# RC_Car_Project_Remote.net
KiCad netlist of a schematic drawn in EasyEDA
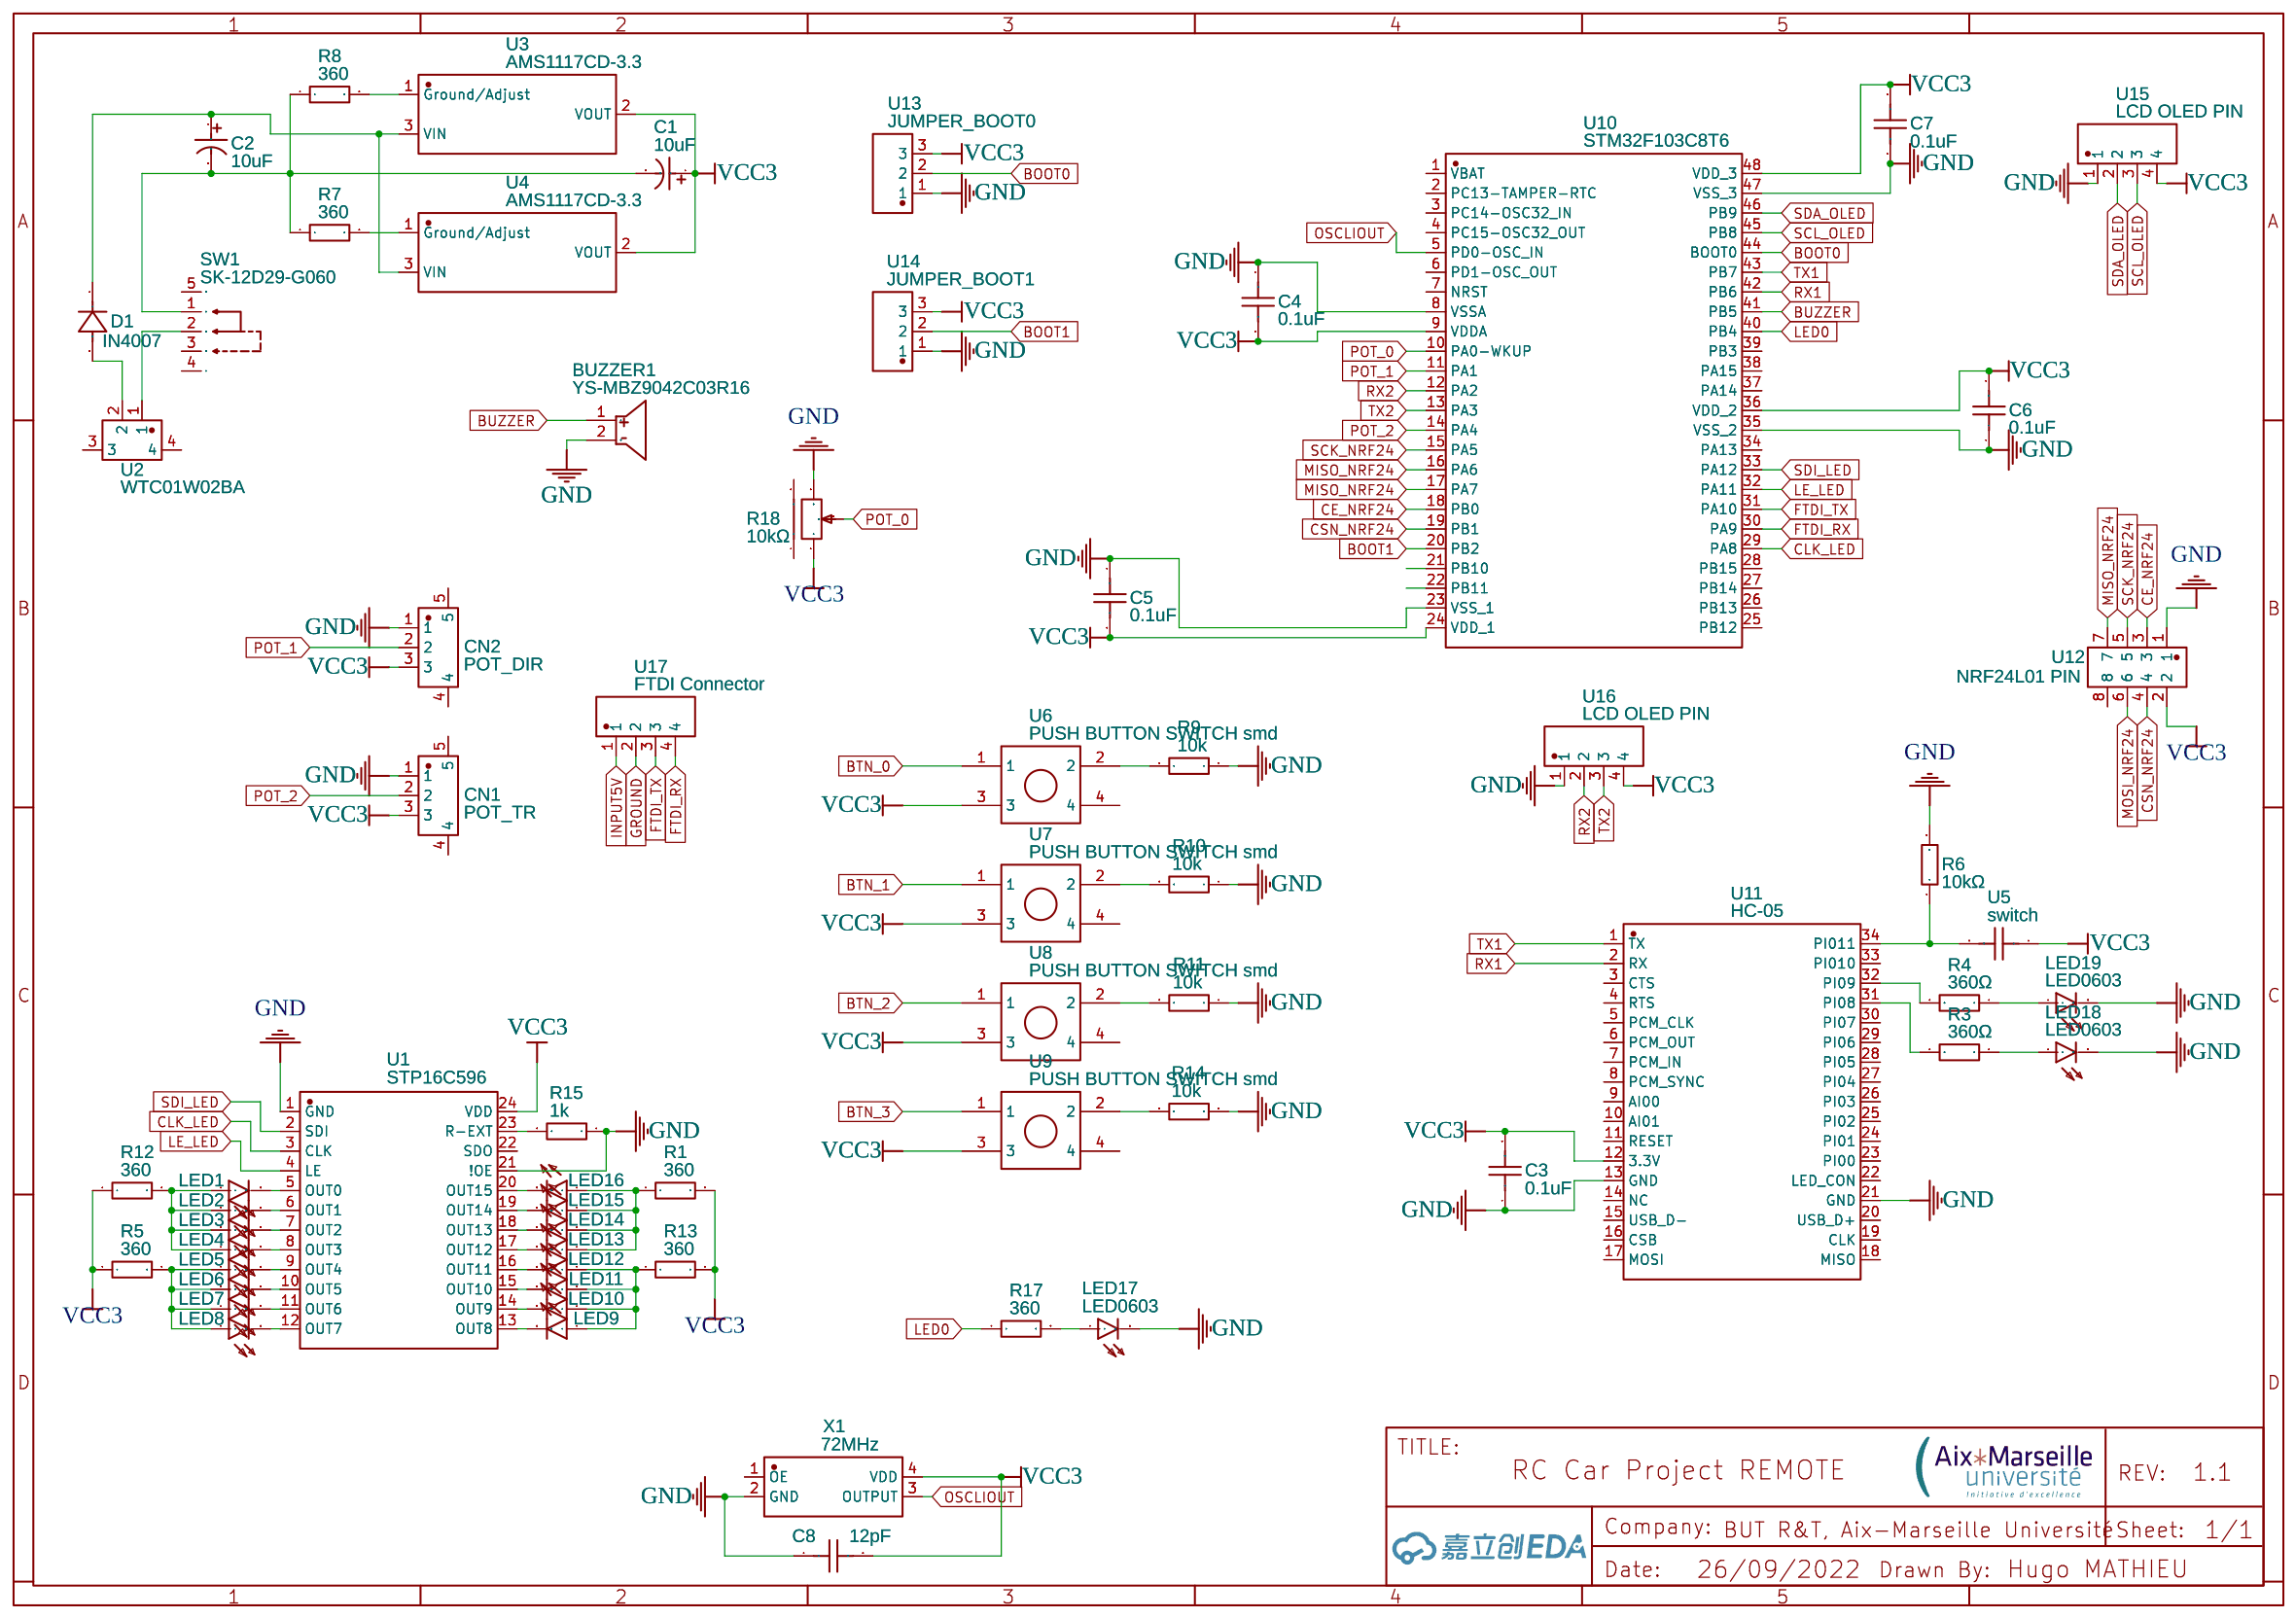
[diagram p0: schematic sheet]

(export (version "E")
  (design (tool "Eeschema 10.0.6"))
  (components
    (comp (ref "BUZZER1")
      (value "YS-MBZ9042C03R16")
      (fields (field (name "BOM_Supplier Part") "C409836"))
      (libsource (lib "") (part "YS-MBZ9042C03R16"))
    )
    (comp (ref "C1")
      (value "10uF")
      (fields
        (field (name "BOM_Manufacturer Part") "RVT1H100M0505")
        (field (name "BOM_Supplier Part") "C72487")
      )
      (libsource (lib "") (part "RVT1H100M0505_1"))
    )
    (comp (ref "C2")
      (value "10uF")
      (fields
        (field (name "BOM_Manufacturer Part") "RVT1H100M0505")
        (field (name "BOM_Supplier Part") "C72487")
      )
      (libsource (lib "") (part "RVT1H100M0505"))
    )
    (comp (ref "C3")
      (value "0.1uF")
      (fields
        (field (name "BOM_Manufacturer Part") "AC0805JRNPO9BN220")
        (field (name "BOM_Supplier Part") "C149614")
      )
      (libsource (lib "") (part "AC0805JRNPO9BN220_2"))
    )
    (comp (ref "C4")
      (value "0.1uF")
      (fields
        (field (name "BOM_Manufacturer Part") "AC0805JRNPO9BN220")
        (field (name "BOM_Supplier Part") "C149614")
      )
      (libsource (lib "") (part "AC0805JRNPO9BN220_1"))
    )
    (comp (ref "C5")
      (value "0.1uF")
      (fields
        (field (name "BOM_Manufacturer Part") "AC0805JRNPO9BN220")
        (field (name "BOM_Supplier Part") "C149614")
      )
      (libsource (lib "") (part "AC0805JRNPO9BN220_1"))
    )
    (comp (ref "C6")
      (value "0.1uF")
      (fields
        (field (name "BOM_Manufacturer Part") "AC0805JRNPO9BN220")
        (field (name "BOM_Supplier Part") "C149614")
      )
      (libsource (lib "") (part "AC0805JRNPO9BN220_2"))
    )
    (comp (ref "C7")
      (value "0.1uF")
      (fields
        (field (name "BOM_Manufacturer Part") "AC0805JRNPO9BN220")
        (field (name "BOM_Supplier Part") "C149614")
      )
      (libsource (lib "") (part "AC0805JRNPO9BN220_2"))
    )
    (comp (ref "C8")
      (value "12pF")
      (fields
        (field (name "BOM_Manufacturer Part") "AC0805JRNPO9BN220")
        (field (name "BOM_Supplier Part") "C149614")
      )
      (libsource (lib "") (part "AC0805JRNPO9BN220"))
    )
    (comp (ref "CN1")
      (value "POT_TR")
      (fields (field (name "BOM_Manufacturer Part") "1.25T-3PWT") (field (name "BOM_Supplier Part") "C22075"))
      (libsource (lib "") (part "1.25T-3PWT"))
    )
    (comp (ref "CN2")
      (value "POT_DIR")
      (fields (field (name "BOM_Manufacturer Part") "1.25T-3PWT") (field (name "BOM_Supplier Part") "C22075"))
      (libsource (lib "") (part "1.25T-3PWT"))
    )
    (comp (ref "D1")
      (value "IN4007")
      (fields (field (name "BOM_Supplier Part") "C9900004719"))
      (libsource (lib "") (part "IN4007"))
    )
    (comp (ref "LED1") (value "LED0603") (libsource (lib "") (part "LED_LEDCHIP-LED0603_1")))
    (comp (ref "LED2") (value "LED0603") (libsource (lib "") (part "LED_LEDCHIP-LED0603_1")))
    (comp (ref "LED3") (value "LED0603") (libsource (lib "") (part "LED_LEDCHIP-LED0603_1")))
    (comp (ref "LED4") (value "LED0603") (libsource (lib "") (part "LED_LEDCHIP-LED0603_1")))
    (comp (ref "LED5") (value "LED0603") (libsource (lib "") (part "LED_LEDCHIP-LED0603_1")))
    (comp (ref "LED6") (value "LED0603") (libsource (lib "") (part "LED_LEDCHIP-LED0603_1")))
    (comp (ref "LED7") (value "LED0603") (libsource (lib "") (part "LED_LEDCHIP-LED0603_1")))
    (comp (ref "LED8") (value "LED0603") (libsource (lib "") (part "LED_LEDCHIP-LED0603_1")))
    (comp (ref "LED9") (value "LED0603") (libsource (lib "") (part "LED_LEDCHIP-LED0603")))
    (comp (ref "LED10") (value "LED0603") (libsource (lib "") (part "LED_LEDCHIP-LED0603")))
    (comp (ref "LED11") (value "LED0603") (libsource (lib "") (part "LED_LEDCHIP-LED0603")))
    (comp (ref "LED12") (value "LED0603") (libsource (lib "") (part "LED_LEDCHIP-LED0603")))
    (comp (ref "LED13") (value "LED0603") (libsource (lib "") (part "LED_LEDCHIP-LED0603")))
    (comp (ref "LED14") (value "LED0603") (libsource (lib "") (part "LED_LEDCHIP-LED0603")))
    (comp (ref "LED15") (value "LED0603") (libsource (lib "") (part "LED_LEDCHIP-LED0603")))
    (comp (ref "LED16") (value "LED0603") (libsource (lib "") (part "LED_LEDCHIP-LED0603")))
    (comp (ref "LED17") (value "LED0603") (libsource (lib "") (part "LED_LEDCHIP-LED0603_1")))
    (comp (ref "LED18") (value "LED0603") (libsource (lib "") (part "LED_LEDCHIP-LED0603_1")))
    (comp (ref "LED19") (value "LED0603") (libsource (lib "") (part "LED_LEDCHIP-LED0603_1")))
    (comp (ref "R1")
      (value "360")
      (fields
        (field (name "BOM_Manufacturer Part") "RC0805FR-07100RL")
        (field (name "BOM_Supplier Part") "C105577")
      )
      (libsource (lib "") (part "RC0805FR-07100RL_1"))
    )
    (comp (ref "R3")
      (value "360Ω")
      (fields
        (field (name "BOM_Manufacturer Part") "1206W4F1002T5E")
        (field (name "BOM_Supplier Part") "C17902")
      )
      (libsource (lib "") (part "1206W4F1002T5E"))
    )
    (comp (ref "R4")
      (value "360Ω")
      (fields
        (field (name "BOM_Manufacturer Part") "1206W4F1002T5E")
        (field (name "BOM_Supplier Part") "C17902")
      )
      (libsource (lib "") (part "1206W4F1002T5E"))
    )
    (comp (ref "R5")
      (value "360")
      (fields
        (field (name "BOM_Manufacturer Part") "RC0805FR-07100RL")
        (field (name "BOM_Supplier Part") "C105577")
      )
      (libsource (lib "") (part "RC0805FR-07100RL_1"))
    )
    (comp (ref "R6")
      (value "10kΩ")
      (fields
        (field (name "BOM_Manufacturer Part") "1206W4F1002T5E")
        (field (name "BOM_Supplier Part") "C17902")
      )
      (libsource (lib "") (part "1206W4F1002T5E_1"))
    )
    (comp (ref "R7")
      (value "360")
      (fields
        (field (name "BOM_Manufacturer Part") "RC0805FR-07100RL")
        (field (name "BOM_Supplier Part") "C105577")
      )
      (libsource (lib "") (part "RC0805FR-07100RL_1"))
    )
    (comp (ref "R8")
      (value "360")
      (fields
        (field (name "BOM_Manufacturer Part") "RC0805FR-07100RL")
        (field (name "BOM_Supplier Part") "C105577")
      )
      (libsource (lib "") (part "RC0805FR-07100RL_1"))
    )
    (comp (ref "R9")
      (value "10k")
      (fields
        (field (name "BOM_Manufacturer Part") "RC0805FR-07100RL")
        (field (name "BOM_Supplier Part") "C105577")
      )
      (libsource (lib "") (part "RC0805FR-07100RL"))
    )
    (comp (ref "R10")
      (value "10k")
      (fields
        (field (name "BOM_Manufacturer Part") "RC0805FR-07100RL")
        (field (name "BOM_Supplier Part") "C105577")
      )
      (libsource (lib "") (part "RC0805FR-07100RL"))
    )
    (comp (ref "R11")
      (value "10k")
      (fields
        (field (name "BOM_Manufacturer Part") "RC0805FR-07100RL")
        (field (name "BOM_Supplier Part") "C105577")
      )
      (libsource (lib "") (part "RC0805FR-07100RL"))
    )
    (comp (ref "R12")
      (value "360")
      (fields
        (field (name "BOM_Manufacturer Part") "RC0805FR-07100RL")
        (field (name "BOM_Supplier Part") "C105577")
      )
      (libsource (lib "") (part "RC0805FR-07100RL_1"))
    )
    (comp (ref "R13")
      (value "360")
      (fields
        (field (name "BOM_Manufacturer Part") "RC0805FR-07100RL")
        (field (name "BOM_Supplier Part") "C105577")
      )
      (libsource (lib "") (part "RC0805FR-07100RL_1"))
    )
    (comp (ref "R14")
      (value "10k")
      (fields
        (field (name "BOM_Manufacturer Part") "RC0805FR-07100RL")
        (field (name "BOM_Supplier Part") "C105577")
      )
      (libsource (lib "") (part "RC0805FR-07100RL"))
    )
    (comp (ref "R15")
      (value "1k")
      (fields
        (field (name "BOM_Manufacturer Part") "RC0805FR-07100RL")
        (field (name "BOM_Supplier Part") "C105577")
      )
      (libsource (lib "") (part "RC0805FR-07100RL"))
    )
    (comp (ref "R17")
      (value "360")
      (fields
        (field (name "BOM_Manufacturer Part") "RC0805FR-07100RL")
        (field (name "BOM_Supplier Part") "C105577")
      )
      (libsource (lib "") (part "RC0805FR-07100RL_1"))
    )
    (comp (ref "R18")
      (value "10kΩ")
      (fields
        (field (name "BOM_Manufacturer Part") "RK09K1130AP5")
        (field (name "BOM_Supplier Part") "C470295")
      )
      (libsource (lib "") (part "RK09K1130AP5"))
    )
    (comp (ref "SW1")
      (value "SK-12D29-G060")
      (fields (field (name "BOM_Supplier Part") "C2848877"))
      (libsource (lib "") (part "SK-12D29-G060"))
    )
    (comp (ref "U1")
      (value "STP16C596")
      (fields (field (name "BOM_Supplier Part") "914-2948"))
      (libsource (lib "") (part "STP16C596"))
    )
    (comp (ref "U2")
      (value "WTC01W02BA")
      (fields (field (name "BOM_Supplier Part") "C5120226"))
      (libsource (lib "") (part "WTC01W02BA"))
    )
    (comp (ref "U3")
      (value "AMS1117CD-3.3")
      (fields (field (name "BOM_Supplier Part") "C841796"))
      (libsource (lib "") (part "AMS1117CD-3.3"))
    )
    (comp (ref "U4")
      (value "AMS1117CD-3.3")
      (fields (field (name "BOM_Supplier Part") "C841796"))
      (libsource (lib "") (part "AMS1117CD-3.3"))
    )
    (comp (ref "U5")
      (value "switch")
      (fields
        (field (name "BOM_Manufacturer Part") "0.5pF-C0805")
        (field (name "BOM_Supplier Part") "C9900009443")
      )
      (libsource (lib "") (part "0.5PF-C0805"))
    )
    (comp (ref "U6")
      (value "PUSH BUTTON SWITCH smd")
      (fields (field (name "BOM_Manufacturer Part") "HALO PUSH BUTTON SWITCH"))
      (libsource (lib "") (part "PUSH BUTTON SWITCH smd"))
    )
    (comp (ref "U7")
      (value "PUSH BUTTON SWITCH smd")
      (fields (field (name "BOM_Manufacturer Part") "HALO PUSH BUTTON SWITCH"))
      (libsource (lib "") (part "PUSH BUTTON SWITCH smd"))
    )
    (comp (ref "U8")
      (value "PUSH BUTTON SWITCH smd")
      (fields (field (name "BOM_Manufacturer Part") "HALO PUSH BUTTON SWITCH"))
      (libsource (lib "") (part "PUSH BUTTON SWITCH smd"))
    )
    (comp (ref "U9")
      (value "PUSH BUTTON SWITCH smd")
      (fields (field (name "BOM_Manufacturer Part") "HALO PUSH BUTTON SWITCH"))
      (libsource (lib "") (part "PUSH BUTTON SWITCH smd"))
    )
    (comp (ref "U10")
      (value "STM32F103C8T6")
      (fields (field (name "BOM_Supplier Part") "C8734"))
      (libsource (lib "") (part "STM32F103C8T6"))
    )
    (comp (ref "U11")
      (value "HC-05")
      (fields (field (name "BOM_Supplier Part") "C9900001063"))
      (libsource (lib "") (part "HC-05"))
    )
    (comp (ref "U12")
      (value "NRF24L01 PIN")
      (fields (field (name "BOM_Manufacturer Part") "2.54-2*4") (field (name "BOM_Supplier Part") "C2977588"))
      (libsource (lib "") (part "2.54-2*4"))
    )
    (comp (ref "U13")
      (value "JUMPER_BOOT0")
      (fields
        (field (name "BOM_Manufacturer Part") "2.54*3单排")
        (field (name "BOM_Supplier Part") "C9900016162")
      )
      (libsource (lib "") (part "2.54*3单排"))
    )
    (comp (ref "U14")
      (value "JUMPER_BOOT1")
      (fields
        (field (name "BOM_Manufacturer Part") "2.54*3单排")
        (field (name "BOM_Supplier Part") "C9900016162")
      )
      (libsource (lib "") (part "2.54*3单排"))
    )
    (comp (ref "U15")
      (value "LCD OLED PIN")
      (fields
        (field (name "BOM_Manufacturer Part") "2.54*4单排")
        (field (name "BOM_Supplier Part") "C9900016163")
      )
      (libsource (lib "") (part "2.54*4单排"))
    )
    (comp (ref "U16")
      (value "LCD OLED PIN")
      (fields
        (field (name "BOM_Manufacturer Part") "2.54*4单排")
        (field (name "BOM_Supplier Part") "C9900016163")
      )
      (libsource (lib "") (part "2.54*4单排"))
    )
    (comp (ref "U17")
      (value "FTDI Connector")
      (fields
        (field (name "BOM_Manufacturer Part") "2.54*4单排")
        (field (name "BOM_Supplier Part") "C9900016163")
      )
      (libsource (lib "") (part "2.54*4单排"))
    )
    (comp (ref "X1")
      (value "72MHz")
      (fields
        (field (name "BOM_Manufacturer Part") "S5D13.560000A20F30T")
        (field (name "BOM_Supplier Part") "C387226")
      )
      (libsource (lib "") (part "S5D13.560000A20F30T"))
    )
  )
  (nets
    (net (code "1") (name "BOOT0") (class "Default")
      (node (ref "U10") (pin "44") (pinfunction "BOOT0_44") (pintype "unspecified"))
      (node (ref "U13") (pin "2") (pinfunction "2_2") (pintype "unspecified"))
    )
    (net (code "2") (name "BOOT1") (class "Default")
      (node (ref "U10") (pin "20") (pinfunction "PB2_20") (pintype "unspecified"))
      (node (ref "U14") (pin "2") (pinfunction "2_2") (pintype "unspecified"))
    )
    (net (code "3") (name "BTN_0") (class "Default")
      (node (ref "U6") (pin "1") (pinfunction "1_1") (pintype "unspecified"))
    )
    (net (code "4") (name "BTN_1") (class "Default")
      (node (ref "U7") (pin "1") (pinfunction "1_1") (pintype "unspecified"))
    )
    (net (code "5") (name "BTN_2") (class "Default")
      (node (ref "U8") (pin "1") (pinfunction "1_1") (pintype "unspecified"))
    )
    (net (code "6") (name "BTN_3") (class "Default")
      (node (ref "U9") (pin "1") (pinfunction "1_1") (pintype "unspecified"))
    )
    (net (code "7") (name "BUZZER") (class "Default")
      (node (ref "BUZZER1") (pin "1") (pinfunction "1_1") (pintype "unspecified"))
      (node (ref "U10") (pin "41") (pinfunction "PB5_41") (pintype "unspecified"))
    )
    (net (code "8") (name "CE_NRF24") (class "Default")
      (node (ref "U10") (pin "18") (pinfunction "PB0_18") (pintype "unspecified"))
      (node (ref "U12") (pin "3") (pinfunction "3_3") (pintype "unspecified"))
    )
    (net (code "9") (name "CLK_LED") (class "Default")
      (node (ref "U1") (pin "3") (pinfunction "CLK_3") (pintype "unspecified"))
      (node (ref "U10") (pin "29") (pinfunction "PA8_29") (pintype "unspecified"))
    )
    (net (code "10") (name "CSN_NRF24") (class "Default")
      (node (ref "U10") (pin "19") (pinfunction "PB1_19") (pintype "unspecified"))
      (node (ref "U12") (pin "4") (pinfunction "4_4") (pintype "unspecified"))
    )
    (net (code "11") (name "FTDI_RX") (class "Default")
      (node (ref "U10") (pin "30") (pinfunction "PA9_30") (pintype "unspecified"))
      (node (ref "U17") (pin "4") (pinfunction "4_4") (pintype "unspecified"))
    )
    (net (code "12") (name "FTDI_TX") (class "Default")
      (node (ref "U10") (pin "31") (pinfunction "PA10_31") (pintype "unspecified"))
      (node (ref "U17") (pin "3") (pinfunction "3_3") (pintype "unspecified"))
    )
    (net (code "13") (name "GND") (class "Default")
      (node (ref "BUZZER1") (pin "2") (pinfunction "2_2") (pintype "unspecified"))
      (node (ref "C3") (pin "1") (pinfunction "1_1") (pintype "unspecified"))
      (node (ref "C4") (pin "1") (pinfunction "1_1") (pintype "unspecified"))
      (node (ref "C5") (pin "1") (pinfunction "1_1") (pintype "unspecified"))
      (node (ref "C6") (pin "1") (pinfunction "1_1") (pintype "unspecified"))
      (node (ref "C7") (pin "1") (pinfunction "1_1") (pintype "unspecified"))
      (node (ref "C8") (pin "1") (pinfunction "1_1") (pintype "unspecified"))
      (node (ref "CN1") (pin "1") (pinfunction "1_1") (pintype "unspecified"))
      (node (ref "CN2") (pin "1") (pinfunction "1_1") (pintype "unspecified"))
      (node (ref "LED17") (pin "C") (pinfunction "C_C") (pintype "bidirectional"))
      (node (ref "LED18") (pin "C") (pinfunction "C_C") (pintype "bidirectional"))
      (node (ref "LED19") (pin "C") (pinfunction "C_C") (pintype "bidirectional"))
      (node (ref "R10") (pin "1") (pinfunction "1_1") (pintype "input"))
      (node (ref "R11") (pin "1") (pinfunction "1_1") (pintype "input"))
      (node (ref "R14") (pin "1") (pinfunction "1_1") (pintype "input"))
      (node (ref "R15") (pin "1") (pinfunction "1_1") (pintype "input"))
      (node (ref "R18") (pin "3") (pinfunction "3_3") (pintype "input"))
      (node (ref "R6") (pin "2") (pinfunction "2_2") (pintype "input"))
      (node (ref "R9") (pin "1") (pinfunction "1_1") (pintype "input"))
      (node (ref "U1") (pin "1") (pinfunction "GND_1") (pintype "unspecified"))
      (node (ref "U1") (pin "21") (pinfunction "!OE_21") (pintype "unspecified"))
      (node (ref "U10") (pin "23") (pinfunction "VSS_1_23") (pintype "unspecified"))
      (node (ref "U10") (pin "35") (pinfunction "VSS_2_35") (pintype "unspecified"))
      (node (ref "U10") (pin "47") (pinfunction "VSS_3_47") (pintype "unspecified"))
      (node (ref "U10") (pin "8") (pinfunction "VSSA_8") (pintype "unspecified"))
      (node (ref "U11") (pin "13") (pinfunction "GND_13") (pintype "unspecified"))
      (node (ref "U11") (pin "21") (pinfunction "GND_21") (pintype "unspecified"))
      (node (ref "U12") (pin "1") (pinfunction "1_1") (pintype "unspecified"))
      (node (ref "U13") (pin "1") (pinfunction "1_1") (pintype "unspecified"))
      (node (ref "U14") (pin "1") (pinfunction "1_1") (pintype "unspecified"))
      (node (ref "U15") (pin "1") (pinfunction "1_1") (pintype "unspecified"))
      (node (ref "U16") (pin "1") (pinfunction "1_1") (pintype "unspecified"))
      (node (ref "X1") (pin "2") (pinfunction "GND_2") (pintype "unspecified"))
    )
    (net (code "14") (name "GROUND") (class "Default")
      (node (ref "U17") (pin "2") (pinfunction "2_2") (pintype "unspecified"))
    )
    (net (code "15") (name "INPUT5V") (class "Default")
      (node (ref "U17") (pin "1") (pinfunction "1_1") (pintype "unspecified"))
    )
    (net (code "16") (name "LED0") (class "Default")
      (node (ref "R17") (pin "1") (pinfunction "1_1") (pintype "input"))
      (node (ref "U10") (pin "40") (pinfunction "PB4_40") (pintype "unspecified"))
    )
    (net (code "17") (name "LE_LED") (class "Default")
      (node (ref "U1") (pin "4") (pinfunction "LE_4") (pintype "unspecified"))
      (node (ref "U10") (pin "32") (pinfunction "PA11_32") (pintype "unspecified"))
    )
    (net (code "18") (name "MISO_NRF24") (class "Default")
      (node (ref "U10") (pin "16") (pinfunction "PA6_16") (pintype "unspecified"))
      (node (ref "U10") (pin "17") (pinfunction "PA7_17") (pintype "unspecified"))
      (node (ref "U12") (pin "7") (pinfunction "7_7") (pintype "unspecified"))
    )
    (net (code "19") (name "MOSI_NRF24") (class "Default")
      (node (ref "U12") (pin "6") (pinfunction "6_6") (pintype "unspecified"))
    )
    (net (code "20") (name "Net-(C1-Pad2)") (class "Default")
      (node (ref "C1") (pin "2") (pinfunction "2_2") (pintype "input"))
      (node (ref "C2") (pin "2") (pinfunction "2_2") (pintype "input"))
      (node (ref "R7") (pin "1") (pinfunction "1_1") (pintype "input"))
      (node (ref "R8") (pin "1") (pinfunction "1_1") (pintype "input"))
      (node (ref "SW1") (pin "1") (pinfunction "1_1") (pintype "unspecified"))
    )
    (net (code "21") (name "Net-(D1-A)") (class "Default")
      (node (ref "D1") (pin "2") (pinfunction "A_2") (pintype "unspecified"))
      (node (ref "U2") (pin "2") (pinfunction "2_2") (pintype "unspecified"))
    )
    (net (code "22") (name "Net-(D1-K)") (class "Default")
      (node (ref "C2") (pin "1") (pinfunction "1_1") (pintype "input"))
      (node (ref "D1") (pin "1") (pinfunction "K_1") (pintype "unspecified"))
      (node (ref "U3") (pin "3") (pinfunction "VIN_3") (pintype "unspecified"))
      (node (ref "U4") (pin "3") (pinfunction "VIN_3") (pintype "unspecified"))
    )
    (net (code "23") (name "Net-(LED1-PadA)") (class "Default")
      (node (ref "LED1") (pin "A") (pinfunction "A_A") (pintype "bidirectional"))
      (node (ref "LED2") (pin "A") (pinfunction "A_A") (pintype "bidirectional"))
      (node (ref "LED3") (pin "A") (pinfunction "A_A") (pintype "bidirectional"))
      (node (ref "LED4") (pin "A") (pinfunction "A_A") (pintype "bidirectional"))
      (node (ref "R12") (pin "2") (pinfunction "2_2") (pintype "input"))
    )
    (net (code "24") (name "Net-(LED5-PadA)") (class "Default")
      (node (ref "LED5") (pin "A") (pinfunction "A_A") (pintype "bidirectional"))
      (node (ref "LED6") (pin "A") (pinfunction "A_A") (pintype "bidirectional"))
      (node (ref "LED7") (pin "A") (pinfunction "A_A") (pintype "bidirectional"))
      (node (ref "LED8") (pin "A") (pinfunction "A_A") (pintype "bidirectional"))
      (node (ref "R5") (pin "2") (pinfunction "2_2") (pintype "input"))
    )
    (net (code "25") (name "Net-(LED10-PadA)") (class "Default")
      (node (ref "LED10") (pin "A") (pinfunction "A_A") (pintype "bidirectional"))
      (node (ref "LED11") (pin "A") (pinfunction "A_A") (pintype "bidirectional"))
      (node (ref "LED12") (pin "A") (pinfunction "A_A") (pintype "bidirectional"))
      (node (ref "LED9") (pin "A") (pinfunction "A_A") (pintype "bidirectional"))
      (node (ref "R13") (pin "1") (pinfunction "1_1") (pintype "input"))
    )
    (net (code "26") (name "Net-(LED13-PadA)") (class "Default")
      (node (ref "LED13") (pin "A") (pinfunction "A_A") (pintype "bidirectional"))
      (node (ref "LED14") (pin "A") (pinfunction "A_A") (pintype "bidirectional"))
      (node (ref "LED15") (pin "A") (pinfunction "A_A") (pintype "bidirectional"))
      (node (ref "LED16") (pin "A") (pinfunction "A_A") (pintype "bidirectional"))
      (node (ref "R1") (pin "1") (pinfunction "1_1") (pintype "input"))
    )
    (net (code "27") (name "Net-(LED17-PadA)") (class "Default")
      (node (ref "LED17") (pin "A") (pinfunction "A_A") (pintype "bidirectional"))
      (node (ref "R17") (pin "2") (pinfunction "2_2") (pintype "input"))
    )
    (net (code "28") (name "Net-(LED18-PadA)") (class "Default")
      (node (ref "LED18") (pin "A") (pinfunction "A_A") (pintype "bidirectional"))
      (node (ref "R3") (pin "1") (pinfunction "1_1") (pintype "input"))
    )
    (net (code "29") (name "Net-(LED19-PadA)") (class "Default")
      (node (ref "LED19") (pin "A") (pinfunction "A_A") (pintype "bidirectional"))
      (node (ref "R4") (pin "1") (pinfunction "1_1") (pintype "input"))
    )
    (net (code "30") (name "Net-(R9-Pad2)") (class "Default")
      (node (ref "R9") (pin "2") (pinfunction "2_2") (pintype "input"))
      (node (ref "U6") (pin "2") (pinfunction "2_2") (pintype "unspecified"))
    )
    (net (code "31") (name "Net-(R10-Pad2)") (class "Default")
      (node (ref "R10") (pin "2") (pinfunction "2_2") (pintype "input"))
      (node (ref "U7") (pin "2") (pinfunction "2_2") (pintype "unspecified"))
    )
    (net (code "32") (name "Net-(R11-Pad2)") (class "Default")
      (node (ref "R11") (pin "2") (pinfunction "2_2") (pintype "input"))
      (node (ref "U8") (pin "2") (pinfunction "2_2") (pintype "unspecified"))
    )
    (net (code "33") (name "Net-(R14-Pad2)") (class "Default")
      (node (ref "R14") (pin "2") (pinfunction "2_2") (pintype "input"))
      (node (ref "U9") (pin "2") (pinfunction "2_2") (pintype "unspecified"))
    )
    (net (code "34") (name "Net-(SW1-Pad2)") (class "Default")
      (node (ref "SW1") (pin "2") (pinfunction "2_2") (pintype "unspecified"))
      (node (ref "U2") (pin "1") (pinfunction "1_1") (pintype "unspecified"))
    )
    (net (code "35") (name "Net-(U1-OUT0)") (class "Default")
      (node (ref "LED1") (pin "C") (pinfunction "C_C") (pintype "bidirectional"))
      (node (ref "U1") (pin "5") (pinfunction "OUT0_5") (pintype "unspecified"))
    )
    (net (code "36") (name "Net-(U1-OUT1)") (class "Default")
      (node (ref "LED2") (pin "C") (pinfunction "C_C") (pintype "bidirectional"))
      (node (ref "U1") (pin "6") (pinfunction "OUT1_6") (pintype "unspecified"))
    )
    (net (code "37") (name "Net-(U1-OUT2)") (class "Default")
      (node (ref "LED3") (pin "C") (pinfunction "C_C") (pintype "bidirectional"))
      (node (ref "U1") (pin "7") (pinfunction "OUT2_7") (pintype "unspecified"))
    )
    (net (code "38") (name "Net-(U1-OUT3)") (class "Default")
      (node (ref "LED4") (pin "C") (pinfunction "C_C") (pintype "bidirectional"))
      (node (ref "U1") (pin "8") (pinfunction "OUT3_8") (pintype "unspecified"))
    )
    (net (code "39") (name "Net-(U1-OUT4)") (class "Default")
      (node (ref "LED5") (pin "C") (pinfunction "C_C") (pintype "bidirectional"))
      (node (ref "U1") (pin "9") (pinfunction "OUT4_9") (pintype "unspecified"))
    )
    (net (code "40") (name "Net-(U1-OUT5)") (class "Default")
      (node (ref "LED6") (pin "C") (pinfunction "C_C") (pintype "bidirectional"))
      (node (ref "U1") (pin "10") (pinfunction "OUT5_10") (pintype "unspecified"))
    )
    (net (code "41") (name "Net-(U1-OUT6)") (class "Default")
      (node (ref "LED7") (pin "C") (pinfunction "C_C") (pintype "bidirectional"))
      (node (ref "U1") (pin "11") (pinfunction "OUT6_11") (pintype "unspecified"))
    )
    (net (code "42") (name "Net-(U1-OUT7)") (class "Default")
      (node (ref "LED8") (pin "C") (pinfunction "C_C") (pintype "bidirectional"))
      (node (ref "U1") (pin "12") (pinfunction "OUT7_12") (pintype "unspecified"))
    )
    (net (code "43") (name "Net-(U1-OUT8)") (class "Default")
      (node (ref "LED9") (pin "C") (pinfunction "C_C") (pintype "bidirectional"))
      (node (ref "U1") (pin "13") (pinfunction "OUT8_13") (pintype "unspecified"))
    )
    (net (code "44") (name "Net-(U1-OUT9)") (class "Default")
      (node (ref "LED10") (pin "C") (pinfunction "C_C") (pintype "bidirectional"))
      (node (ref "U1") (pin "14") (pinfunction "OUT9_14") (pintype "unspecified"))
    )
    (net (code "45") (name "Net-(U1-OUT10)") (class "Default")
      (node (ref "LED11") (pin "C") (pinfunction "C_C") (pintype "bidirectional"))
      (node (ref "U1") (pin "15") (pinfunction "OUT10_15") (pintype "unspecified"))
    )
    (net (code "46") (name "Net-(U1-OUT11)") (class "Default")
      (node (ref "LED12") (pin "C") (pinfunction "C_C") (pintype "bidirectional"))
      (node (ref "U1") (pin "16") (pinfunction "OUT11_16") (pintype "unspecified"))
    )
    (net (code "47") (name "Net-(U1-OUT12)") (class "Default")
      (node (ref "LED13") (pin "C") (pinfunction "C_C") (pintype "bidirectional"))
      (node (ref "U1") (pin "17") (pinfunction "OUT12_17") (pintype "unspecified"))
    )
    (net (code "48") (name "Net-(U1-OUT13)") (class "Default")
      (node (ref "LED14") (pin "C") (pinfunction "C_C") (pintype "bidirectional"))
      (node (ref "U1") (pin "18") (pinfunction "OUT13_18") (pintype "unspecified"))
    )
    (net (code "49") (name "Net-(U1-OUT14)") (class "Default")
      (node (ref "LED15") (pin "C") (pinfunction "C_C") (pintype "bidirectional"))
      (node (ref "U1") (pin "19") (pinfunction "OUT14_19") (pintype "unspecified"))
    )
    (net (code "50") (name "Net-(U1-OUT15)") (class "Default")
      (node (ref "LED16") (pin "C") (pinfunction "C_C") (pintype "bidirectional"))
      (node (ref "U1") (pin "20") (pinfunction "OUT15_20") (pintype "unspecified"))
    )
    (net (code "51") (name "Net-(U1-R-EXT)") (class "Default")
      (node (ref "R15") (pin "2") (pinfunction "2_2") (pintype "input"))
      (node (ref "U1") (pin "23") (pinfunction "R-EXT_23") (pintype "unspecified"))
    )
    (net (code "52") (name "Net-(U3-Ground{slash}Adjust)") (class "Default")
      (node (ref "R8") (pin "2") (pinfunction "2_2") (pintype "input"))
      (node (ref "U3") (pin "1") (pinfunction "Ground/Adjust_1") (pintype "unspecified"))
    )
    (net (code "53") (name "Net-(U4-Ground{slash}Adjust)") (class "Default")
      (node (ref "R7") (pin "2") (pinfunction "2_2") (pintype "input"))
      (node (ref "U4") (pin "1") (pinfunction "Ground/Adjust_1") (pintype "unspecified"))
    )
    (net (code "54") (name "Net-(U11-PI08)") (class "Default")
      (node (ref "R3") (pin "2") (pinfunction "2_2") (pintype "input"))
      (node (ref "U11") (pin "31") (pinfunction "PI08_31") (pintype "unspecified"))
    )
    (net (code "55") (name "Net-(U11-PI09)") (class "Default")
      (node (ref "R4") (pin "2") (pinfunction "2_2") (pintype "input"))
      (node (ref "U11") (pin "32") (pinfunction "PI09_32") (pintype "unspecified"))
    )
    (net (code "56") (name "Net-(U11-PI011)") (class "Default")
      (node (ref "R6") (pin "1") (pinfunction "1_1") (pintype "input"))
      (node (ref "U11") (pin "34") (pinfunction "PI011_34") (pintype "unspecified"))
      (node (ref "U5") (pin "2") (pinfunction "2_2") (pintype "unspecified"))
    )
    (net (code "57") (name "OSCLIOUT") (class "Default")
      (node (ref "U10") (pin "5") (pinfunction "PD0-OSC_IN_5") (pintype "unspecified"))
      (node (ref "X1") (pin "3") (pinfunction "OUTPUT_3") (pintype "unspecified"))
    )
    (net (code "58") (name "POT_0") (class "Default")
      (node (ref "R18") (pin "2") (pinfunction "2_2") (pintype "input"))
      (node (ref "U10") (pin "10") (pinfunction "PA0-WKUP_10") (pintype "unspecified"))
    )
    (net (code "59") (name "POT_1") (class "Default")
      (node (ref "CN2") (pin "2") (pinfunction "2_2") (pintype "unspecified"))
      (node (ref "U10") (pin "11") (pinfunction "PA1_11") (pintype "unspecified"))
    )
    (net (code "60") (name "POT_2") (class "Default")
      (node (ref "CN1") (pin "2") (pinfunction "2_2") (pintype "unspecified"))
      (node (ref "U10") (pin "14") (pinfunction "PA4_14") (pintype "unspecified"))
    )
    (net (code "61") (name "RX1") (class "Default")
      (node (ref "U10") (pin "42") (pinfunction "PB6_42") (pintype "unspecified"))
      (node (ref "U11") (pin "2") (pinfunction "RX_2") (pintype "unspecified"))
    )
    (net (code "62") (name "RX2") (class "Default")
      (node (ref "U10") (pin "12") (pinfunction "PA2_12") (pintype "unspecified"))
      (node (ref "U16") (pin "2") (pinfunction "2_2") (pintype "unspecified"))
    )
    (net (code "63") (name "SCK_NRF24") (class "Default")
      (node (ref "U10") (pin "15") (pinfunction "PA5_15") (pintype "unspecified"))
      (node (ref "U12") (pin "5") (pinfunction "5_5") (pintype "unspecified"))
    )
    (net (code "64") (name "SCL_OLED") (class "Default")
      (node (ref "U10") (pin "45") (pinfunction "PB8_45") (pintype "unspecified"))
      (node (ref "U15") (pin "3") (pinfunction "3_3") (pintype "unspecified"))
    )
    (net (code "65") (name "SDA_OLED") (class "Default")
      (node (ref "U10") (pin "46") (pinfunction "PB9_46") (pintype "unspecified"))
      (node (ref "U15") (pin "2") (pinfunction "2_2") (pintype "unspecified"))
    )
    (net (code "66") (name "SDI_LED") (class "Default")
      (node (ref "U1") (pin "2") (pinfunction "SDI_2") (pintype "unspecified"))
      (node (ref "U10") (pin "33") (pinfunction "PA12_33") (pintype "unspecified"))
    )
    (net (code "67") (name "TX1") (class "Default")
      (node (ref "U10") (pin "43") (pinfunction "PB7_43") (pintype "unspecified"))
      (node (ref "U11") (pin "1") (pinfunction "TX_1") (pintype "unspecified"))
    )
    (net (code "68") (name "TX2") (class "Default")
      (node (ref "U10") (pin "13") (pinfunction "PA3_13") (pintype "unspecified"))
      (node (ref "U16") (pin "3") (pinfunction "3_3") (pintype "unspecified"))
    )
    (net (code "69") (name "VCC3") (class "Default")
      (node (ref "C1") (pin "1") (pinfunction "1_1") (pintype "input"))
      (node (ref "C3") (pin "2") (pinfunction "2_2") (pintype "unspecified"))
      (node (ref "C4") (pin "2") (pinfunction "2_2") (pintype "unspecified"))
      (node (ref "C5") (pin "2") (pinfunction "2_2") (pintype "unspecified"))
      (node (ref "C6") (pin "2") (pinfunction "2_2") (pintype "unspecified"))
      (node (ref "C7") (pin "2") (pinfunction "2_2") (pintype "unspecified"))
      (node (ref "C8") (pin "2") (pinfunction "2_2") (pintype "unspecified"))
      (node (ref "CN1") (pin "3") (pinfunction "3_3") (pintype "unspecified"))
      (node (ref "CN2") (pin "3") (pinfunction "3_3") (pintype "unspecified"))
      (node (ref "R1") (pin "2") (pinfunction "2_2") (pintype "input"))
      (node (ref "R12") (pin "1") (pinfunction "1_1") (pintype "input"))
      (node (ref "R13") (pin "2") (pinfunction "2_2") (pintype "input"))
      (node (ref "R18") (pin "1") (pinfunction "1_1") (pintype "input"))
      (node (ref "R5") (pin "1") (pinfunction "1_1") (pintype "input"))
      (node (ref "U1") (pin "24") (pinfunction "VDD_24") (pintype "unspecified"))
      (node (ref "U10") (pin "24") (pinfunction "VDD_1_24") (pintype "unspecified"))
      (node (ref "U10") (pin "36") (pinfunction "VDD_2_36") (pintype "unspecified"))
      (node (ref "U10") (pin "48") (pinfunction "VDD_3_48") (pintype "unspecified"))
      (node (ref "U10") (pin "9") (pinfunction "VDDA_9") (pintype "unspecified"))
      (node (ref "U11") (pin "12") (pinfunction "3.3V_12") (pintype "unspecified"))
      (node (ref "U12") (pin "2") (pinfunction "2_2") (pintype "unspecified"))
      (node (ref "U13") (pin "3") (pinfunction "3_3") (pintype "unspecified"))
      (node (ref "U14") (pin "3") (pinfunction "3_3") (pintype "unspecified"))
      (node (ref "U15") (pin "4") (pinfunction "4_4") (pintype "unspecified"))
      (node (ref "U16") (pin "4") (pinfunction "4_4") (pintype "unspecified"))
      (node (ref "U3") (pin "2") (pinfunction "VOUT_2") (pintype "unspecified"))
      (node (ref "U4") (pin "2") (pinfunction "VOUT_2") (pintype "unspecified"))
      (node (ref "U5") (pin "1") (pinfunction "1_1") (pintype "unspecified"))
      (node (ref "U6") (pin "3") (pinfunction "3_3") (pintype "unspecified"))
      (node (ref "U7") (pin "3") (pinfunction "3_3") (pintype "unspecified"))
      (node (ref "U8") (pin "3") (pinfunction "3_3") (pintype "unspecified"))
      (node (ref "U9") (pin "3") (pinfunction "3_3") (pintype "unspecified"))
      (node (ref "X1") (pin "4") (pinfunction "VDD_4") (pintype "unspecified"))
    )
    (net (code "70") (name "unconnected-(CN1-Pad4)") (class "Default")
      (node (ref "CN1") (pin "4") (pinfunction "4_4") (pintype "unspecified"))
    )
    (net (code "71") (name "unconnected-(CN1-Pad5)") (class "Default")
      (node (ref "CN1") (pin "5") (pinfunction "5_5") (pintype "unspecified"))
    )
    (net (code "72") (name "unconnected-(CN2-Pad4)") (class "Default")
      (node (ref "CN2") (pin "4") (pinfunction "4_4") (pintype "unspecified"))
    )
    (net (code "73") (name "unconnected-(CN2-Pad5)") (class "Default")
      (node (ref "CN2") (pin "5") (pinfunction "5_5") (pintype "unspecified"))
    )
    (net (code "74") (name "unconnected-(R18-Pad4)") (class "Default")
      (node (ref "R18") (pin "4") (pinfunction "4_4") (pintype "input"))
    )
    (net (code "75") (name "unconnected-(R18-Pad5)") (class "Default")
      (node (ref "R18") (pin "5") (pinfunction "5_5") (pintype "input"))
    )
    (net (code "76") (name "unconnected-(SW1-Pad3)") (class "Default")
      (node (ref "SW1") (pin "3") (pinfunction "3_3") (pintype "unspecified"))
    )
    (net (code "77") (name "unconnected-(SW1-Pad4)") (class "Default")
      (node (ref "SW1") (pin "4") (pinfunction "4_4") (pintype "unspecified"))
    )
    (net (code "78") (name "unconnected-(SW1-Pad5)") (class "Default")
      (node (ref "SW1") (pin "5") (pinfunction "5_5") (pintype "unspecified"))
    )
    (net (code "79") (name "unconnected-(U1-SDO-Pad22)") (class "Default")
      (node (ref "U1") (pin "22") (pinfunction "SDO_22") (pintype "unspecified"))
    )
    (net (code "80") (name "unconnected-(U2-Pad3)") (class "Default")
      (node (ref "U2") (pin "3") (pinfunction "3_3") (pintype "unspecified"))
    )
    (net (code "81") (name "unconnected-(U2-Pad4)") (class "Default")
      (node (ref "U2") (pin "4") (pinfunction "4_4") (pintype "unspecified"))
    )
    (net (code "82") (name "unconnected-(U6-Pad4)") (class "Default")
      (node (ref "U6") (pin "4") (pinfunction "4_4") (pintype "unspecified"))
    )
    (net (code "83") (name "unconnected-(U7-Pad4)") (class "Default")
      (node (ref "U7") (pin "4") (pinfunction "4_4") (pintype "unspecified"))
    )
    (net (code "84") (name "unconnected-(U8-Pad4)") (class "Default")
      (node (ref "U8") (pin "4") (pinfunction "4_4") (pintype "unspecified"))
    )
    (net (code "85") (name "unconnected-(U9-Pad4)") (class "Default")
      (node (ref "U9") (pin "4") (pinfunction "4_4") (pintype "unspecified"))
    )
    (net (code "86") (name "unconnected-(U10-NRST-Pad7)") (class "Default")
      (node (ref "U10") (pin "7") (pinfunction "NRST_7") (pintype "unspecified"))
    )
    (net (code "87") (name "unconnected-(U10-PA13-Pad34)") (class "Default")
      (node (ref "U10") (pin "34") (pinfunction "PA13_34") (pintype "unspecified"))
    )
    (net (code "88") (name "unconnected-(U10-PA14-Pad37)") (class "Default")
      (node (ref "U10") (pin "37") (pinfunction "PA14_37") (pintype "unspecified"))
    )
    (net (code "89") (name "unconnected-(U10-PA15-Pad38)") (class "Default")
      (node (ref "U10") (pin "38") (pinfunction "PA15_38") (pintype "unspecified"))
    )
    (net (code "90") (name "unconnected-(U10-PB3-Pad39)") (class "Default")
      (node (ref "U10") (pin "39") (pinfunction "PB3_39") (pintype "unspecified"))
    )
    (net (code "91") (name "unconnected-(U10-PB10-Pad21)") (class "Default")
      (node (ref "U10") (pin "21") (pinfunction "PB10_21") (pintype "unspecified"))
    )
    (net (code "92") (name "unconnected-(U10-PB11-Pad22)") (class "Default")
      (node (ref "U10") (pin "22") (pinfunction "PB11_22") (pintype "unspecified"))
    )
    (net (code "93") (name "unconnected-(U10-PB12-Pad25)") (class "Default")
      (node (ref "U10") (pin "25") (pinfunction "PB12_25") (pintype "unspecified"))
    )
    (net (code "94") (name "unconnected-(U10-PB13-Pad26)") (class "Default")
      (node (ref "U10") (pin "26") (pinfunction "PB13_26") (pintype "unspecified"))
    )
    (net (code "95") (name "unconnected-(U10-PB14-Pad27)") (class "Default")
      (node (ref "U10") (pin "27") (pinfunction "PB14_27") (pintype "unspecified"))
    )
    (net (code "96") (name "unconnected-(U10-PB15-Pad28)") (class "Default")
      (node (ref "U10") (pin "28") (pinfunction "PB15_28") (pintype "unspecified"))
    )
    (net (code "97") (name "unconnected-(U10-PC13-TAMPER-RTC-Pad2)") (class "Default")
      (node (ref "U10") (pin "2") (pinfunction "PC13-TAMPER-RTC_2") (pintype "unspecified"))
    )
    (net (code "98") (name "unconnected-(U10-PC14-OSC32_IN-Pad3)") (class "Default")
      (node (ref "U10") (pin "3") (pinfunction "PC14-OSC32_IN_3") (pintype "unspecified"))
    )
    (net (code "99") (name "unconnected-(U10-PC15-OSC32_OUT-Pad4)") (class "Default")
      (node (ref "U10") (pin "4") (pinfunction "PC15-OSC32_OUT_4") (pintype "unspecified"))
    )
    (net (code "100") (name "unconnected-(U10-PD1-OSC_OUT-Pad6)") (class "Default")
      (node (ref "U10") (pin "6") (pinfunction "PD1-OSC_OUT_6") (pintype "unspecified"))
    )
    (net (code "101") (name "unconnected-(U10-VBAT-Pad1)") (class "Default")
      (node (ref "U10") (pin "1") (pinfunction "VBAT_1") (pintype "unspecified"))
    )
    (net (code "102") (name "unconnected-(U11-AI00-Pad9)") (class "Default")
      (node (ref "U11") (pin "9") (pinfunction "AI00_9") (pintype "unspecified"))
    )
    (net (code "103") (name "unconnected-(U11-AI01-Pad10)") (class "Default")
      (node (ref "U11") (pin "10") (pinfunction "AI01_10") (pintype "unspecified"))
    )
    (net (code "104") (name "unconnected-(U11-CLK-Pad19)") (class "Default")
      (node (ref "U11") (pin "19") (pinfunction "CLK_19") (pintype "unspecified"))
    )
    (net (code "105") (name "unconnected-(U11-CSB-Pad16)") (class "Default")
      (node (ref "U11") (pin "16") (pinfunction "CSB_16") (pintype "unspecified"))
    )
    (net (code "106") (name "unconnected-(U11-CTS-Pad3)") (class "Default")
      (node (ref "U11") (pin "3") (pinfunction "CTS_3") (pintype "unspecified"))
    )
    (net (code "107") (name "unconnected-(U11-LED_CON-Pad22)") (class "Default")
      (node (ref "U11") (pin "22") (pinfunction "LED_CON_22") (pintype "unspecified"))
    )
    (net (code "108") (name "unconnected-(U11-MISO-Pad18)") (class "Default")
      (node (ref "U11") (pin "18") (pinfunction "MISO_18") (pintype "unspecified"))
    )
    (net (code "109") (name "unconnected-(U11-MOSI-Pad17)") (class "Default")
      (node (ref "U11") (pin "17") (pinfunction "MOSI_17") (pintype "unspecified"))
    )
    (net (code "110") (name "unconnected-(U11-NC-Pad14)") (class "Default")
      (node (ref "U11") (pin "14") (pinfunction "NC_14") (pintype "unspecified"))
    )
    (net (code "111") (name "unconnected-(U11-PCM_CLK-Pad5)") (class "Default")
      (node (ref "U11") (pin "5") (pinfunction "PCM_CLK_5") (pintype "unspecified"))
    )
    (net (code "112") (name "unconnected-(U11-PCM_IN-Pad7)") (class "Default")
      (node (ref "U11") (pin "7") (pinfunction "PCM_IN_7") (pintype "unspecified"))
    )
    (net (code "113") (name "unconnected-(U11-PCM_OUT-Pad6)") (class "Default")
      (node (ref "U11") (pin "6") (pinfunction "PCM_OUT_6") (pintype "unspecified"))
    )
    (net (code "114") (name "unconnected-(U11-PCM_SYNC-Pad8)") (class "Default")
      (node (ref "U11") (pin "8") (pinfunction "PCM_SYNC_8") (pintype "unspecified"))
    )
    (net (code "115") (name "unconnected-(U11-PI00-Pad23)") (class "Default")
      (node (ref "U11") (pin "23") (pinfunction "PI00_23") (pintype "unspecified"))
    )
    (net (code "116") (name "unconnected-(U11-PI01-Pad24)") (class "Default")
      (node (ref "U11") (pin "24") (pinfunction "PI01_24") (pintype "unspecified"))
    )
    (net (code "117") (name "unconnected-(U11-PI02-Pad25)") (class "Default")
      (node (ref "U11") (pin "25") (pinfunction "PI02_25") (pintype "unspecified"))
    )
    (net (code "118") (name "unconnected-(U11-PI03-Pad26)") (class "Default")
      (node (ref "U11") (pin "26") (pinfunction "PI03_26") (pintype "unspecified"))
    )
    (net (code "119") (name "unconnected-(U11-PI04-Pad27)") (class "Default")
      (node (ref "U11") (pin "27") (pinfunction "PI04_27") (pintype "unspecified"))
    )
    (net (code "120") (name "unconnected-(U11-PI05-Pad28)") (class "Default")
      (node (ref "U11") (pin "28") (pinfunction "PI05_28") (pintype "unspecified"))
    )
    (net (code "121") (name "unconnected-(U11-PI06-Pad29)") (class "Default")
      (node (ref "U11") (pin "29") (pinfunction "PI06_29") (pintype "unspecified"))
    )
    (net (code "122") (name "unconnected-(U11-PI07-Pad30)") (class "Default")
      (node (ref "U11") (pin "30") (pinfunction "PI07_30") (pintype "unspecified"))
    )
    (net (code "123") (name "unconnected-(U11-PI010-Pad33)") (class "Default")
      (node (ref "U11") (pin "33") (pinfunction "PI010_33") (pintype "unspecified"))
    )
    (net (code "124") (name "unconnected-(U11-RESET-Pad11)") (class "Default")
      (node (ref "U11") (pin "11") (pinfunction "RESET_11") (pintype "unspecified"))
    )
    (net (code "125") (name "unconnected-(U11-RTS-Pad4)") (class "Default")
      (node (ref "U11") (pin "4") (pinfunction "RTS_4") (pintype "unspecified"))
    )
    (net (code "126") (name "unconnected-(U11-USB_D+-Pad20)") (class "Default")
      (node (ref "U11") (pin "20") (pinfunction "USB_D+_20") (pintype "unspecified"))
    )
    (net (code "127") (name "unconnected-(U11-USB_D--Pad15)") (class "Default")
      (node (ref "U11") (pin "15") (pinfunction "USB_D-_15") (pintype "unspecified"))
    )
    (net (code "128") (name "unconnected-(U12-Pad8)") (class "Default")
      (node (ref "U12") (pin "8") (pinfunction "8_8") (pintype "unspecified"))
    )
    (net (code "129") (name "unconnected-(X1-OE-Pad1)") (class "Default")
      (node (ref "X1") (pin "1") (pinfunction "OE_1") (pintype "unspecified"))
    )
  )
)
